# Awesome-Shield-0_5.net
KiCad netlist of a schematic drawn in EAGLE
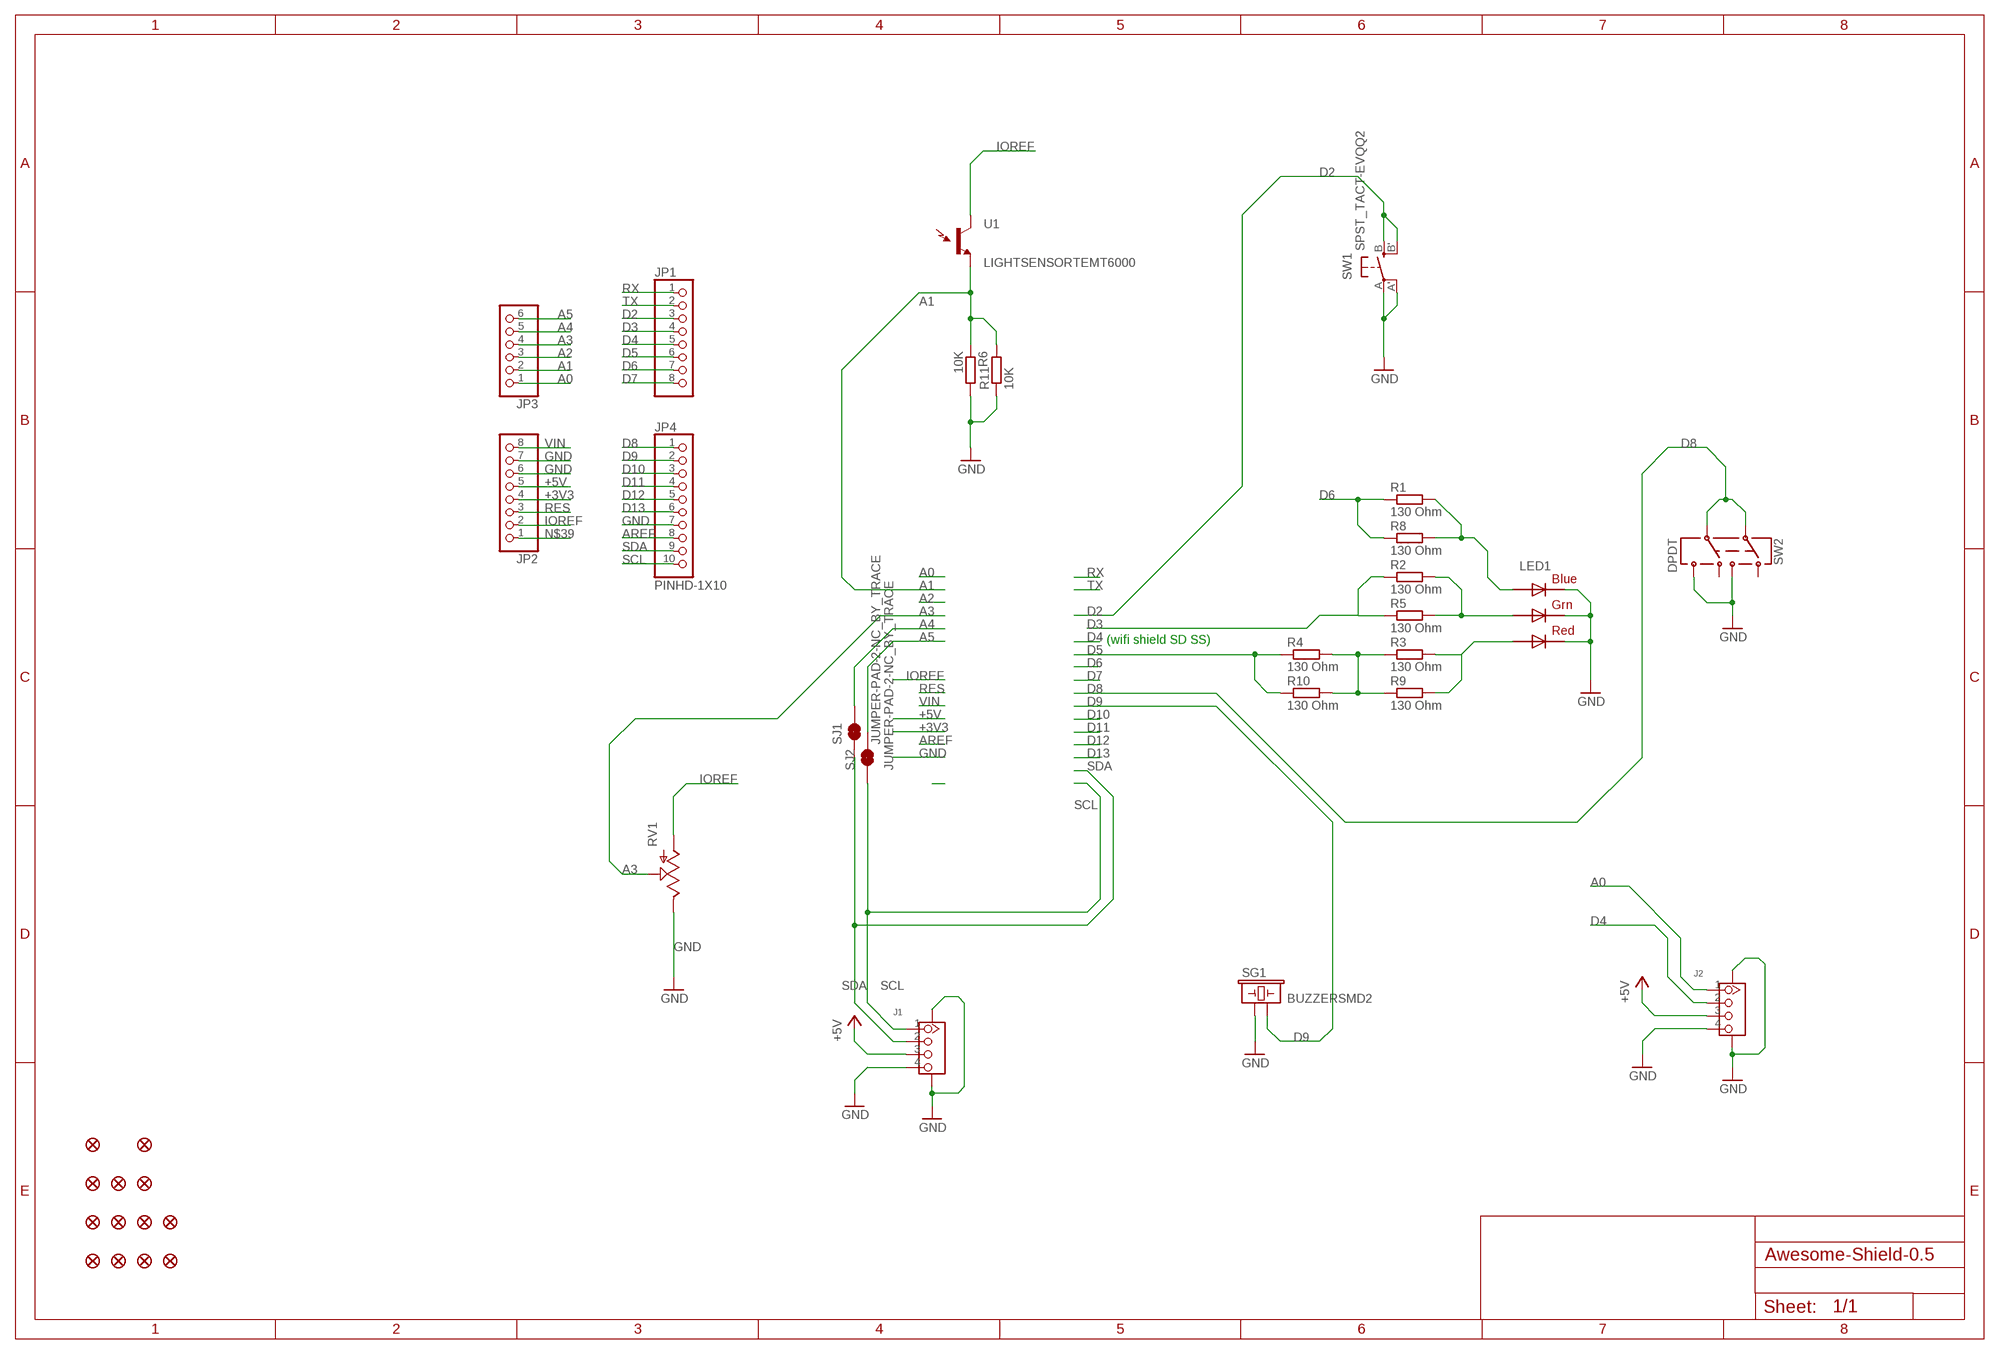
[diagram p0: schematic, sheet 1]

(export (version "E")
  (design (tool "Eeschema 10.0.6"))
  (components
    (comp (ref "FID1")
      (value "FIDUCIAL1X2")
      (footprint "eagle-import:FIDUCIAL-1X2")
      (libsource (lib "eagle-import") (part "FIDUCIAL1X2"))
    )
    (comp (ref "FID2")
      (value "FIDUCIAL1X2")
      (footprint "eagle-import:FIDUCIAL-1X2")
      (libsource (lib "eagle-import") (part "FIDUCIAL1X2"))
    )
    (comp (ref "FID3")
      (value "FIDUCIAL1X2")
      (footprint "eagle-import:FIDUCIAL-1X2")
      (libsource (lib "eagle-import") (part "FIDUCIAL1X2"))
    )
    (comp (ref "FID4")
      (value "FIDUCIAL1X2")
      (footprint "eagle-import:FIDUCIAL-1X2")
      (libsource (lib "eagle-import") (part "FIDUCIAL1X2"))
    )
    (comp (ref "FID5")
      (value "FIDUCIALUFIDUCIAL")
      (footprint "eagle-import:MICRO-FIDUCIAL")
      (libsource (lib "eagle-import") (part "FIDUCIALUFIDUCIAL"))
    )
    (comp (ref "FID6")
      (value "FIDUCIALUFIDUCIAL")
      (footprint "eagle-import:MICRO-FIDUCIAL")
      (libsource (lib "eagle-import") (part "FIDUCIALUFIDUCIAL"))
    )
    (comp (ref "FID7")
      (value "FIDUCIALUFIDUCIAL")
      (footprint "eagle-import:MICRO-FIDUCIAL")
      (libsource (lib "eagle-import") (part "FIDUCIALUFIDUCIAL"))
    )
    (comp (ref "FID8")
      (value "FIDUCIALUFIDUCIAL")
      (footprint "eagle-import:MICRO-FIDUCIAL")
      (libsource (lib "eagle-import") (part "FIDUCIALUFIDUCIAL"))
    )
    (comp (ref "FID9")
      (value "FIDUCIALUFIDUCIAL")
      (footprint "eagle-import:MICRO-FIDUCIAL")
      (libsource (lib "eagle-import") (part "FIDUCIALUFIDUCIAL"))
    )
    (comp (ref "FID10")
      (value "FIDUCIALUFIDUCIAL")
      (footprint "eagle-import:MICRO-FIDUCIAL")
      (libsource (lib "eagle-import") (part "FIDUCIALUFIDUCIAL"))
    )
    (comp (ref "FID11")
      (value "FIDUCIALUFIDUCIAL")
      (footprint "eagle-import:MICRO-FIDUCIAL")
      (libsource (lib "eagle-import") (part "FIDUCIALUFIDUCIAL"))
    )
    (comp (ref "FID13")
      (value "FIDUCIALUFIDUCIAL")
      (footprint "eagle-import:MICRO-FIDUCIAL")
      (libsource (lib "eagle-import") (part "FIDUCIALUFIDUCIAL"))
    )
    (comp (ref "FID15")
      (value "FIDUCIALUFIDUCIAL")
      (footprint "eagle-import:MICRO-FIDUCIAL")
      (libsource (lib "eagle-import") (part "FIDUCIALUFIDUCIAL"))
    )
    (comp (ref "J1")
      (value "GROVE-CONNECTOR-SMD(4+2P-2.0)")
      (footprint "eagle-import:HW4-SMD-2.0")
      (libsource (lib "eagle-import") (part "GROVE-CONNECTOR-SMD(4+2P-2.0)"))
    )
    (comp (ref "J2")
      (value "GROVE-CONNECTOR-SMD(4+2P-2.0)")
      (footprint "eagle-import:HW4-SMD-2.0")
      (libsource (lib "eagle-import") (part "GROVE-CONNECTOR-SMD(4+2P-2.0)"))
    )
    (comp (ref "JP1")
      (value "PINHD-1X8CLEANBIG")
      (footprint "eagle-import:1X08-CLEANBIG")
      (libsource (lib "eagle-import") (part "PINHD-1X8CLEANBIG"))
    )
    (comp (ref "JP2")
      (value "PINHD-1X8CLEANBIG")
      (footprint "eagle-import:1X08-CLEANBIG")
      (libsource (lib "eagle-import") (part "PINHD-1X8CLEANBIG"))
    )
    (comp (ref "JP3")
      (value "PINHD-1X6CLEAN")
      (footprint "eagle-import:1X06-CLEAN")
      (libsource (lib "eagle-import") (part "PINHD-1X6CLEAN"))
    )
    (comp (ref "JP4")
      (value "PINHD-1X10")
      (footprint "eagle-import:1X10-BIG")
      (libsource (lib "eagle-import") (part "PINHD-1X10"))
    )
    (comp (ref "LED1")
      (value "RGBLED5050")
      (footprint "eagle-import:RGBLED5050")
      (libsource (lib "eagle-import") (part "RGBLED5050"))
    )
    (comp (ref "R1")
      (value "130 Ohm")
      (footprint "eagle-import:R1206")
      (libsource (lib "eagle-import") (part "R-EU_R1206"))
    )
    (comp (ref "R2")
      (value "130 Ohm")
      (footprint "eagle-import:R1206")
      (libsource (lib "eagle-import") (part "R-EU_R1206"))
    )
    (comp (ref "R3")
      (value "130 Ohm")
      (footprint "eagle-import:R1206")
      (libsource (lib "eagle-import") (part "R-EU_R1206"))
    )
    (comp (ref "R4")
      (value "130 Ohm")
      (footprint "eagle-import:R1206")
      (libsource (lib "eagle-import") (part "R-EU_R1206"))
    )
    (comp (ref "R5")
      (value "130 Ohm")
      (footprint "eagle-import:R0603")
      (libsource (lib "eagle-import") (part "R-EU_R0603"))
    )
    (comp (ref "R6")
      (value "10K")
      (footprint "eagle-import:R1206")
      (libsource (lib "eagle-import") (part "R-EU_R1206"))
    )
    (comp (ref "R8")
      (value "130 Ohm")
      (footprint "eagle-import:R0603")
      (libsource (lib "eagle-import") (part "R-EU_R0603"))
    )
    (comp (ref "R9")
      (value "130 Ohm")
      (footprint "eagle-import:R0603")
      (libsource (lib "eagle-import") (part "R-EU_R0603"))
    )
    (comp (ref "R10")
      (value "130 Ohm")
      (footprint "eagle-import:R0603")
      (libsource (lib "eagle-import") (part "R-EU_R0603"))
    )
    (comp (ref "R11")
      (value "10K")
      (footprint "eagle-import:R0603")
      (libsource (lib "eagle-import") (part "R-EU_R0603"))
    )
    (comp (ref "RV1")
      (value "POT")
      (footprint "eagle-import:ALPS_POT")
      (libsource (lib "eagle-import") (part "POT"))
    )
    (comp (ref "SG1")
      (value "BUZZERSMD2")
      (footprint "eagle-import:BUZZER-CCV")
      (libsource (lib "eagle-import") (part "BUZZERSMD2"))
    )
    (comp (ref "SJ1")
      (value "JUMPER-PAD-2-NC_BY_TRACE")
      (footprint "eagle-import:PAD-JUMPER-2-NC_BY_TRACE_YES_SILK")
      (libsource (lib "eagle-import") (part "JUMPER-PAD-2-NC_BY_TRACE"))
    )
    (comp (ref "SJ2")
      (value "JUMPER-PAD-2-NC_BY_TRACE")
      (footprint "eagle-import:PAD-JUMPER-2-NC_BY_TRACE_YES_SILK")
      (libsource (lib "eagle-import") (part "JUMPER-PAD-2-NC_BY_TRACE"))
    )
    (comp (ref "SW1")
      (value "SPST_TACT-EVQQ2")
      (footprint "eagle-import:EVQ-Q2")
      (libsource (lib "eagle-import") (part "SPST_TACT-EVQQ2"))
    )
    (comp (ref "SW2")
      (value "DPDT")
      (footprint "eagle-import:AYZ0202")
      (libsource (lib "eagle-import") (part "SWITCH-DPDTAYZ0202"))
    )
    (comp (ref "U1")
      (value "LIGHTSENSORTEMT6000")
      (footprint "eagle-import:TEMT6000-SEN")
      (libsource (lib "eagle-import") (part "LIGHTSENSORTEMT6000"))
    )
  )
  (nets
    (net (code "1") (name "+5V") (class "Default")
      (node (ref "J1") (pin "3") (pinfunction "3_3") (pintype "bidirectional"))
      (node (ref "J2") (pin "3") (pinfunction "3_3") (pintype "bidirectional"))
      (node (ref "JP2") (pin "5") (pinfunction "5_5") (pintype "passive"))
    )
    (net (code "2") (name "/+3V3") (class "Default")
      (node (ref "JP2") (pin "4") (pinfunction "4_4") (pintype "passive"))
    )
    (net (code "3") (name "/A0") (class "Default")
      (node (ref "J2") (pin "1") (pinfunction "1_1") (pintype "bidirectional"))
      (node (ref "JP3") (pin "1") (pinfunction "1_1") (pintype "passive"))
    )
    (net (code "4") (name "/A1") (class "Default")
      (node (ref "JP3") (pin "2") (pinfunction "2_2") (pintype "passive"))
      (node (ref "R11") (pin "2") (pinfunction "2_2") (pintype "passive"))
      (node (ref "R6") (pin "1") (pinfunction "1_1") (pintype "passive"))
      (node (ref "U1") (pin "EMITTER") (pinfunction "E1_EMITTER") (pintype "passive"))
    )
    (net (code "5") (name "/A2") (class "Default")
      (node (ref "JP3") (pin "3") (pinfunction "3_3") (pintype "passive"))
    )
    (net (code "6") (name "/A3") (class "Default")
      (node (ref "JP3") (pin "4") (pinfunction "4_4") (pintype "passive"))
      (node (ref "RV1") (pin "P$2") (pinfunction "S_P$2") (pintype "passive"))
    )
    (net (code "7") (name "/A4") (class "Default")
      (node (ref "JP3") (pin "5") (pinfunction "5_5") (pintype "passive"))
      (node (ref "SJ1") (pin "2") (pinfunction "2_2") (pintype "passive"))
    )
    (net (code "8") (name "/A5") (class "Default")
      (node (ref "JP3") (pin "6") (pinfunction "6_6") (pintype "passive"))
      (node (ref "SJ2") (pin "2") (pinfunction "2_2") (pintype "passive"))
    )
    (net (code "9") (name "/AREF") (class "Default")
      (node (ref "JP4") (pin "8") (pinfunction "8_8") (pintype "passive"))
    )
    (net (code "10") (name "/D2") (class "Default")
      (node (ref "JP1") (pin "3") (pinfunction "3_3") (pintype "passive"))
      (node (ref "SW1") (pin "B") (pinfunction "S_B") (pintype "passive"))
      (node (ref "SW1") (pin "B'") (pinfunction "S1_B'") (pintype "passive"))
    )
    (net (code "11") (name "/D3") (class "Default")
      (node (ref "JP1") (pin "4") (pinfunction "4_4") (pintype "passive"))
      (node (ref "R2") (pin "1") (pinfunction "1_1") (pintype "passive"))
      (node (ref "R5") (pin "1") (pinfunction "1_1") (pintype "passive"))
    )
    (net (code "12") (name "/D4") (class "Default")
      (node (ref "J2") (pin "2") (pinfunction "2_2") (pintype "bidirectional"))
      (node (ref "JP1") (pin "5") (pinfunction "5_5") (pintype "passive"))
    )
    (net (code "13") (name "/D5") (class "Default")
      (node (ref "JP1") (pin "6") (pinfunction "6_6") (pintype "passive"))
      (node (ref "R10") (pin "1") (pinfunction "1_1") (pintype "passive"))
      (node (ref "R4") (pin "1") (pinfunction "1_1") (pintype "passive"))
    )
    (net (code "14") (name "/D6") (class "Default")
      (node (ref "JP1") (pin "7") (pinfunction "7_7") (pintype "passive"))
      (node (ref "R1") (pin "1") (pinfunction "1_1") (pintype "passive"))
      (node (ref "R8") (pin "1") (pinfunction "1_1") (pintype "passive"))
    )
    (net (code "15") (name "/D7") (class "Default")
      (node (ref "JP1") (pin "8") (pinfunction "8_8") (pintype "passive"))
    )
    (net (code "16") (name "/D8") (class "Default")
      (node (ref "JP4") (pin "1") (pinfunction "1_1") (pintype "passive"))
      (node (ref "SW2") (pin "2") (pinfunction "2_2") (pintype "bidirectional"))
      (node (ref "SW2") (pin "5") (pinfunction "5_5") (pintype "bidirectional"))
    )
    (net (code "17") (name "/D9") (class "Default")
      (node (ref "JP4") (pin "2") (pinfunction "2_2") (pintype "passive"))
      (node (ref "SG1") (pin "-") (pinfunction "2_-") (pintype "passive"))
    )
    (net (code "18") (name "/D10") (class "Default")
      (node (ref "JP4") (pin "3") (pinfunction "3_3") (pintype "passive"))
    )
    (net (code "19") (name "/D11") (class "Default")
      (node (ref "JP4") (pin "4") (pinfunction "4_4") (pintype "passive"))
    )
    (net (code "20") (name "/D12") (class "Default")
      (node (ref "JP4") (pin "5") (pinfunction "5_5") (pintype "passive"))
    )
    (net (code "21") (name "/D13") (class "Default")
      (node (ref "JP4") (pin "6") (pinfunction "6_6") (pintype "passive"))
    )
    (net (code "22") (name "/IOREF") (class "Default")
      (node (ref "JP2") (pin "2") (pinfunction "2_2") (pintype "passive"))
      (node (ref "RV1") (pin "P$3") (pinfunction "A_P$3") (pintype "passive"))
      (node (ref "U1") (pin "COLLECTOR") (pinfunction "C1_COLLECTOR") (pintype "passive"))
    )
    (net (code "23") (name "/N$39") (class "Default")
      (node (ref "JP2") (pin "1") (pinfunction "1_1") (pintype "passive"))
    )
    (net (code "24") (name "/RES") (class "Default")
      (node (ref "JP2") (pin "3") (pinfunction "3_3") (pintype "passive"))
    )
    (net (code "25") (name "/RX") (class "Default")
      (node (ref "JP1") (pin "1") (pinfunction "1_1") (pintype "passive"))
    )
    (net (code "26") (name "/SCL") (class "Default")
      (node (ref "J1") (pin "1") (pinfunction "1_1") (pintype "bidirectional"))
      (node (ref "JP4") (pin "10") (pinfunction "10_10") (pintype "passive"))
      (node (ref "SJ2") (pin "1") (pinfunction "1_1") (pintype "passive"))
    )
    (net (code "27") (name "/SDA") (class "Default")
      (node (ref "J1") (pin "2") (pinfunction "2_2") (pintype "bidirectional"))
      (node (ref "JP4") (pin "9") (pinfunction "9_9") (pintype "passive"))
      (node (ref "SJ1") (pin "1") (pinfunction "1_1") (pintype "passive"))
    )
    (net (code "28") (name "/TX") (class "Default")
      (node (ref "JP1") (pin "2") (pinfunction "2_2") (pintype "passive"))
    )
    (net (code "29") (name "/VIN") (class "Default")
      (node (ref "JP2") (pin "8") (pinfunction "8_8") (pintype "passive"))
    )
    (net (code "30") (name "GND") (class "Default")
      (node (ref "J1") (pin "4") (pinfunction "4_4") (pintype "bidirectional"))
      (node (ref "J1") (pin "SS1") (pinfunction "SS1_SS1") (pintype "bidirectional"))
      (node (ref "J1") (pin "SS2") (pinfunction "SS2_SS2") (pintype "bidirectional"))
      (node (ref "J2") (pin "4") (pinfunction "4_4") (pintype "bidirectional"))
      (node (ref "J2") (pin "SS1") (pinfunction "SS1_SS1") (pintype "bidirectional"))
      (node (ref "J2") (pin "SS2") (pinfunction "SS2_SS2") (pintype "bidirectional"))
      (node (ref "JP2") (pin "6") (pinfunction "6_6") (pintype "passive"))
      (node (ref "JP2") (pin "7") (pinfunction "7_7") (pintype "passive"))
      (node (ref "JP4") (pin "7") (pinfunction "7_7") (pintype "passive"))
      (node (ref "LED1") (pin "4") (pinfunction "BLUE_C_4") (pintype "bidirectional"))
      (node (ref "LED1") (pin "5") (pinfunction "RED_C_5") (pintype "bidirectional"))
      (node (ref "LED1") (pin "6") (pinfunction "GREEN_C_6") (pintype "bidirectional"))
      (node (ref "R11") (pin "1") (pinfunction "1_1") (pintype "passive"))
      (node (ref "R6") (pin "2") (pinfunction "2_2") (pintype "passive"))
      (node (ref "RV1") (pin "P$1") (pinfunction "E_P$1") (pintype "passive"))
      (node (ref "SG1") (pin "+") (pinfunction "1_+") (pintype "passive"))
      (node (ref "SW1") (pin "A") (pinfunction "P_A") (pintype "passive"))
      (node (ref "SW1") (pin "A'") (pinfunction "P1_A'") (pintype "passive"))
      (node (ref "SW2") (pin "3") (pinfunction "3_3") (pintype "bidirectional"))
      (node (ref "SW2") (pin "6") (pinfunction "6_6") (pintype "bidirectional"))
    )
    (net (code "31") (name "Net-(LED1-BLUE_A)") (class "Default")
      (node (ref "LED1") (pin "3") (pinfunction "BLUE_A_3") (pintype "bidirectional"))
      (node (ref "R1") (pin "2") (pinfunction "2_2") (pintype "passive"))
      (node (ref "R8") (pin "2") (pinfunction "2_2") (pintype "passive"))
    )
    (net (code "32") (name "Net-(LED1-GREEN_A)") (class "Default")
      (node (ref "LED1") (pin "1") (pinfunction "GREEN_A_1") (pintype "bidirectional"))
      (node (ref "R2") (pin "2") (pinfunction "2_2") (pintype "passive"))
      (node (ref "R5") (pin "2") (pinfunction "2_2") (pintype "passive"))
    )
    (net (code "33") (name "Net-(LED1-RED_A)") (class "Default")
      (node (ref "LED1") (pin "2") (pinfunction "RED_A_2") (pintype "bidirectional"))
      (node (ref "R3") (pin "2") (pinfunction "2_2") (pintype "passive"))
      (node (ref "R9") (pin "2") (pinfunction "2_2") (pintype "passive"))
    )
    (net (code "34") (name "Net-(R10-Pad2)") (class "Default")
      (node (ref "R10") (pin "2") (pinfunction "2_2") (pintype "passive"))
      (node (ref "R3") (pin "1") (pinfunction "1_1") (pintype "passive"))
      (node (ref "R4") (pin "2") (pinfunction "2_2") (pintype "passive"))
      (node (ref "R9") (pin "1") (pinfunction "1_1") (pintype "passive"))
    )
    (net (code "35") (name "unconnected-(SW2-Pad1)") (class "Default")
      (node (ref "SW2") (pin "1") (pinfunction "1_1") (pintype "bidirectional"))
    )
    (net (code "36") (name "unconnected-(SW2-Pad4)") (class "Default")
      (node (ref "SW2") (pin "4") (pinfunction "4_4") (pintype "bidirectional"))
    )
  )
)
